# 7G_controller.net
KiCad netlist of a schematic drawn in EAGLE
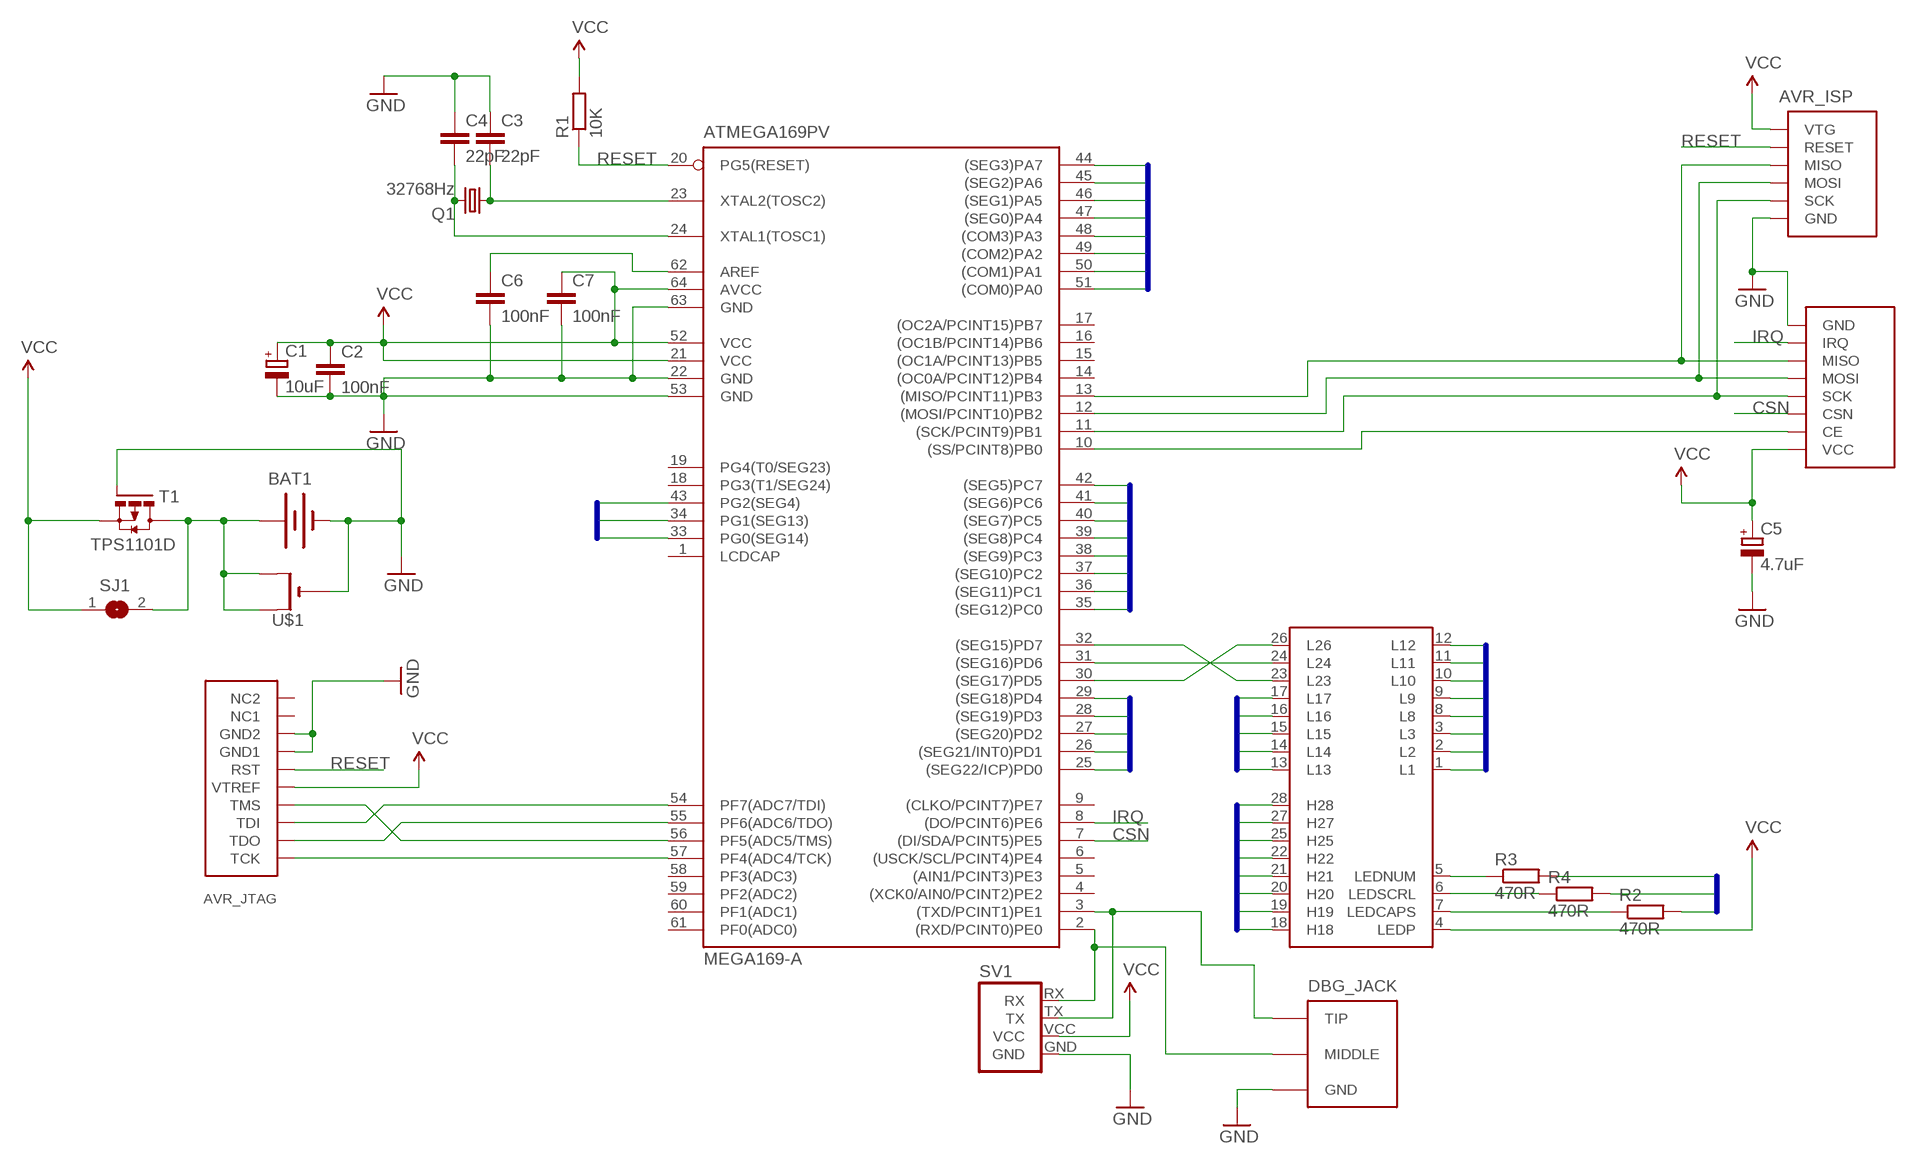
[diagram p0: schematic, sheet 1]

(export (version "E")
  (design (tool "Eeschema 10.0.6"))
  (components
    (comp (ref "ATMEGA169PV")
      (value "MEGA169-A")
      (footprint "eagle-import:TQFP64")
      (fields (field (name "MPN") "ATMEGA169PV-8AU"))
      (libsource (lib "eagle-import") (part "MEGA169-A"))
    )
    (comp (ref "AVR_ISP")
      (value "AVR-ISP-6SMALL_FP")
      (footprint "eagle-import:AVR-ISP-6-SMALL-FP")
      (libsource (lib "eagle-import") (part "AVR-ISP-6SMALL_FP"))
    )
    (comp (ref "AVR_JTAG")
      (value "AVR-JTAG")
      (footprint "eagle-import:AVR-JTAG")
      (libsource (lib "eagle-import") (part "AVR-JTAG"))
    )
    (comp (ref "BAT1")
      (value "BATTERYPLAIN")
      (footprint "eagle-import:BATTERY")
      (libsource (lib "eagle-import") (part "BATTERYPLAIN"))
    )
    (comp (ref "C1")
      (value "10uF")
      (footprint "eagle-import:SMC_B")
      (libsource (lib "eagle-import") (part "CPOL-EUSMCB"))
    )
    (comp (ref "C2")
      (value "100nF")
      (footprint "eagle-import:C0805")
      (libsource (lib "eagle-import") (part "C-EUC0805"))
    )
    (comp (ref "C3")
      (value "22pF")
      (footprint "eagle-import:C0805")
      (libsource (lib "eagle-import") (part "C-EUC0805"))
    )
    (comp (ref "C4")
      (value "22pF")
      (footprint "eagle-import:C0805")
      (libsource (lib "eagle-import") (part "C-EUC0805"))
    )
    (comp (ref "C5")
      (value "4.7uF")
      (footprint "eagle-import:SMC_B")
      (libsource (lib "eagle-import") (part "CPOL-EUSMCB"))
    )
    (comp (ref "C6")
      (value "100nF")
      (footprint "eagle-import:C0805")
      (libsource (lib "eagle-import") (part "C-EUC0805"))
    )
    (comp (ref "C7")
      (value "100nF")
      (footprint "eagle-import:C0805")
      (libsource (lib "eagle-import") (part "C-EUC0805"))
    )
    (comp (ref "DBG_JACK")
      (value "JACK_FEMALE_3.5MMCHEAP")
      (footprint "eagle-import:JACK_CHEAP")
      (libsource (lib "eagle-import") (part "JACK_FEMALE_3.5MMCHEAP"))
    )
    (comp (ref "MTRX_CONN")
      (value "SS7G_CONNSMD")
      (footprint "eagle-import:SS7G_CONN_SMD")
      (libsource (lib "eagle-import") (part "SS7G_CONNSMD"))
    )
    (comp (ref "NRF24L01")
      (value "NRF24L01_MOD_NINE_EAGLESGENERIC")
      (footprint "eagle-import:NRF24L01_MOD_GENERIC")
      (libsource (lib "eagle-import") (part "NRF24L01_MOD_NINE_EAGLESGENERIC"))
    )
    (comp (ref "Q1")
      (value "32768Hz")
      (footprint "eagle-import:NSK_QUARTZ_CLOCK")
      (libsource (lib "eagle-import") (part "CRYSTAL"))
    )
    (comp (ref "R1")
      (value "10K")
      (footprint "eagle-import:R0805")
      (libsource (lib "eagle-import") (part "R-EU_R0805"))
    )
    (comp (ref "R2")
      (value "470R")
      (footprint "eagle-import:R0805")
      (libsource (lib "eagle-import") (part "R-EU_R0805"))
    )
    (comp (ref "R3")
      (value "470R")
      (footprint "eagle-import:R0805")
      (libsource (lib "eagle-import") (part "R-EU_R0805"))
    )
    (comp (ref "R4")
      (value "470R")
      (footprint "eagle-import:R0805")
      (libsource (lib "eagle-import") (part "R-EU_R0805"))
    )
    (comp (ref "SJ1") (value "SJ") (footprint "eagle-import:SJ") (libsource (lib "eagle-import") (part "SJ")))
    (comp (ref "SV1")
      (value "UART_PORT")
      (footprint "eagle-import:UART_PORT")
      (libsource (lib "eagle-import") (part "UART_PORT"))
    )
    (comp (ref "T1")
      (value "TPS1101D")
      (footprint "eagle-import:SO8")
      (libsource (lib "eagle-import") (part "TPS1101D"))
    )
    (comp (ref "U$1")
      (value "CR2032SMT")
      (footprint "eagle-import:CR2032-SMD")
      (libsource (lib "eagle-import") (part "CR2032SMT"))
    )
  )
  (nets
    (net (code "1") (name "/CAPS") (class "Default")
      (node (ref "ATMEGA169PV") (pin "43") (pinfunction "PG2(SEG4)_43") (pintype "bidirectional"))
      (node (ref "R2") (pin "2") (pinfunction "2_2") (pintype "passive"))
    )
    (net (code "2") (name "/CSN") (class "Default")
      (node (ref "ATMEGA169PV") (pin "7") (pinfunction "(DI/SDA/PCINT5)PE5_7") (pintype "bidirectional"))
      (node (ref "NRF24L01") (pin "CSN") (pinfunction "CSN_CSN") (pintype "input"))
    )
    (net (code "3") (name "/H18") (class "Default")
      (node (ref "ATMEGA169PV") (pin "42") (pinfunction "(SEG5)PC7_42") (pintype "output"))
      (node (ref "MTRX_CONN") (pin "18") (pinfunction "H18_18") (pintype "bidirectional"))
    )
    (net (code "4") (name "/H19") (class "Default")
      (node (ref "ATMEGA169PV") (pin "41") (pinfunction "(SEG6)PC6_41") (pintype "output"))
      (node (ref "MTRX_CONN") (pin "19") (pinfunction "H19_19") (pintype "bidirectional"))
    )
    (net (code "5") (name "/H20") (class "Default")
      (node (ref "ATMEGA169PV") (pin "40") (pinfunction "(SEG7)PC5_40") (pintype "output"))
      (node (ref "MTRX_CONN") (pin "20") (pinfunction "H20_20") (pintype "bidirectional"))
    )
    (net (code "6") (name "/H21") (class "Default")
      (node (ref "ATMEGA169PV") (pin "38") (pinfunction "(SEG9)PC3_38") (pintype "output"))
      (node (ref "MTRX_CONN") (pin "21") (pinfunction "H21_21") (pintype "bidirectional"))
    )
    (net (code "7") (name "/H22") (class "Default")
      (node (ref "ATMEGA169PV") (pin "36") (pinfunction "(SEG11)PC1_36") (pintype "output"))
      (node (ref "MTRX_CONN") (pin "22") (pinfunction "H22_22") (pintype "bidirectional"))
    )
    (net (code "8") (name "/H25") (class "Default")
      (node (ref "ATMEGA169PV") (pin "35") (pinfunction "(SEG12)PC0_35") (pintype "output"))
      (node (ref "MTRX_CONN") (pin "25") (pinfunction "H25_25") (pintype "bidirectional"))
    )
    (net (code "9") (name "/H27") (class "Default")
      (node (ref "ATMEGA169PV") (pin "37") (pinfunction "(SEG10)PC2_37") (pintype "output"))
      (node (ref "MTRX_CONN") (pin "27") (pinfunction "H27_27") (pintype "bidirectional"))
    )
    (net (code "10") (name "/H28") (class "Default")
      (node (ref "ATMEGA169PV") (pin "39") (pinfunction "(SEG8)PC4_39") (pintype "output"))
      (node (ref "MTRX_CONN") (pin "28") (pinfunction "H28_28") (pintype "bidirectional"))
    )
    (net (code "11") (name "/IRQ") (class "Default")
      (node (ref "ATMEGA169PV") (pin "8") (pinfunction "(DO/PCINT6)PE6_8") (pintype "bidirectional"))
      (node (ref "NRF24L01") (pin "IRQ") (pinfunction "IRQ_IRQ") (pintype "output"))
    )
    (net (code "12") (name "/L1") (class "Default")
      (node (ref "ATMEGA169PV") (pin "50") (pinfunction "(COM1)PA1_50") (pintype "bidirectional"))
      (node (ref "MTRX_CONN") (pin "1") (pinfunction "L1_1") (pintype "bidirectional"))
    )
    (net (code "13") (name "/L2") (class "Default")
      (node (ref "ATMEGA169PV") (pin "48") (pinfunction "(COM3)PA3_48") (pintype "bidirectional"))
      (node (ref "MTRX_CONN") (pin "2") (pinfunction "L2_2") (pintype "bidirectional"))
    )
    (net (code "14") (name "/L3") (class "Default")
      (node (ref "ATMEGA169PV") (pin "46") (pinfunction "(SEG1)PA5_46") (pintype "bidirectional"))
      (node (ref "MTRX_CONN") (pin "3") (pinfunction "L3_3") (pintype "bidirectional"))
    )
    (net (code "15") (name "/L8") (class "Default")
      (node (ref "ATMEGA169PV") (pin "45") (pinfunction "(SEG2)PA6_45") (pintype "bidirectional"))
      (node (ref "MTRX_CONN") (pin "8") (pinfunction "L8_8") (pintype "bidirectional"))
    )
    (net (code "16") (name "/L9") (class "Default")
      (node (ref "ATMEGA169PV") (pin "44") (pinfunction "(SEG3)PA7_44") (pintype "bidirectional"))
      (node (ref "MTRX_CONN") (pin "9") (pinfunction "L9_9") (pintype "bidirectional"))
    )
    (net (code "17") (name "/L10") (class "Default")
      (node (ref "ATMEGA169PV") (pin "25") (pinfunction "(SEG22/ICP)PD0_25") (pintype "bidirectional"))
      (node (ref "MTRX_CONN") (pin "10") (pinfunction "L10_10") (pintype "bidirectional"))
    )
    (net (code "18") (name "/L11") (class "Default")
      (node (ref "ATMEGA169PV") (pin "26") (pinfunction "(SEG21/INT0)PD1_26") (pintype "bidirectional"))
      (node (ref "MTRX_CONN") (pin "11") (pinfunction "L11_11") (pintype "bidirectional"))
    )
    (net (code "19") (name "/L12") (class "Default")
      (node (ref "ATMEGA169PV") (pin "27") (pinfunction "(SEG20)PD2_27") (pintype "bidirectional"))
      (node (ref "MTRX_CONN") (pin "12") (pinfunction "L12_12") (pintype "bidirectional"))
    )
    (net (code "20") (name "/L13") (class "Default")
      (node (ref "ATMEGA169PV") (pin "28") (pinfunction "(SEG19)PD3_28") (pintype "bidirectional"))
      (node (ref "MTRX_CONN") (pin "13") (pinfunction "L13_13") (pintype "bidirectional"))
    )
    (net (code "21") (name "/L14") (class "Default")
      (node (ref "ATMEGA169PV") (pin "29") (pinfunction "(SEG18)PD4_29") (pintype "bidirectional"))
      (node (ref "MTRX_CONN") (pin "14") (pinfunction "L14_14") (pintype "bidirectional"))
    )
    (net (code "22") (name "/L15") (class "Default")
      (node (ref "ATMEGA169PV") (pin "51") (pinfunction "(COM0)PA0_51") (pintype "bidirectional"))
      (node (ref "MTRX_CONN") (pin "15") (pinfunction "L15_15") (pintype "bidirectional"))
    )
    (net (code "23") (name "/L16") (class "Default")
      (node (ref "ATMEGA169PV") (pin "49") (pinfunction "(COM2)PA2_49") (pintype "bidirectional"))
      (node (ref "MTRX_CONN") (pin "16") (pinfunction "L16_16") (pintype "bidirectional"))
    )
    (net (code "24") (name "/L17") (class "Default")
      (node (ref "ATMEGA169PV") (pin "47") (pinfunction "(SEG0)PA4_47") (pintype "bidirectional"))
      (node (ref "MTRX_CONN") (pin "17") (pinfunction "L17_17") (pintype "bidirectional"))
    )
    (net (code "25") (name "/NUML") (class "Default")
      (node (ref "ATMEGA169PV") (pin "33") (pinfunction "PG0(SEG14)_33") (pintype "bidirectional"))
      (node (ref "R3") (pin "2") (pinfunction "2_2") (pintype "passive"))
    )
    (net (code "26") (name "/RESET") (class "Default")
      (node (ref "ATMEGA169PV") (pin "20") (pinfunction "PG5(RESET)_20") (pintype "input"))
      (node (ref "AVR_ISP") (pin "RESET") (pinfunction "RESET_RESET") (pintype "passive"))
      (node (ref "AVR_JTAG") (pin "P$6") (pinfunction "RST_P$6") (pintype "bidirectional"))
      (node (ref "R1") (pin "1") (pinfunction "1_1") (pintype "passive"))
    )
    (net (code "27") (name "/SCRL") (class "Default")
      (node (ref "ATMEGA169PV") (pin "34") (pinfunction "PG1(SEG13)_34") (pintype "bidirectional"))
      (node (ref "R4") (pin "2") (pinfunction "2_2") (pintype "passive"))
    )
    (net (code "28") (name "GND") (class "Default")
      (node (ref "ATMEGA169PV") (pin "22") (pinfunction "GND_22") (pintype "power_in"))
      (node (ref "ATMEGA169PV") (pin "53") (pinfunction "GND_53") (pintype "power_in"))
      (node (ref "ATMEGA169PV") (pin "63") (pinfunction "GND_63") (pintype "power_in"))
      (node (ref "AVR_ISP") (pin "GND") (pinfunction "GND_GND") (pintype "passive"))
      (node (ref "AVR_JTAG") (pin "P$10") (pinfunction "GND2_P$10") (pintype "power_in"))
      (node (ref "AVR_JTAG") (pin "P$2") (pinfunction "GND1_P$2") (pintype "power_in"))
      (node (ref "BAT1") (pin "-") (pinfunction "-_-") (pintype "power_in"))
      (node (ref "C1") (pin "-") (pinfunction "-_-") (pintype "passive"))
      (node (ref "C2") (pin "2") (pinfunction "2_2") (pintype "passive"))
      (node (ref "C3") (pin "1") (pinfunction "1_1") (pintype "passive"))
      (node (ref "C4") (pin "1") (pinfunction "1_1") (pintype "passive"))
      (node (ref "C5") (pin "-") (pinfunction "-_-") (pintype "passive"))
      (node (ref "C6") (pin "2") (pinfunction "2_2") (pintype "passive"))
      (node (ref "C7") (pin "2") (pinfunction "2_2") (pintype "passive"))
      (node (ref "DBG_JACK") (pin "1") (pinfunction "GND_1") (pintype "bidirectional"))
      (node (ref "NRF24L01") (pin "GND") (pinfunction "GND_GND") (pintype "power_in"))
      (node (ref "SV1") (pin "GND") (pinfunction "GND_GND") (pintype "passive"))
      (node (ref "T1") (pin "4") (pinfunction "G_4") (pintype "passive"))
      (node (ref "U$1") (pin "-") (pinfunction "-_-") (pintype "passive"))
    )
    (net (code "29") (name "Net-(ATMEGA169PV-(MISO{slash}PCINT11)PB3)") (class "Default")
      (node (ref "ATMEGA169PV") (pin "13") (pinfunction "(MISO/PCINT11)PB3_13") (pintype "bidirectional"))
      (node (ref "AVR_ISP") (pin "MISO") (pinfunction "MISO_MISO") (pintype "passive"))
      (node (ref "NRF24L01") (pin "MISO") (pinfunction "MISO_MISO") (pintype "output"))
    )
    (net (code "30") (name "Net-(ATMEGA169PV-(MOSI{slash}PCINT10)PB2)") (class "Default")
      (node (ref "ATMEGA169PV") (pin "12") (pinfunction "(MOSI/PCINT10)PB2_12") (pintype "bidirectional"))
      (node (ref "AVR_ISP") (pin "MOSI") (pinfunction "MOSI_MOSI") (pintype "passive"))
      (node (ref "NRF24L01") (pin "MOSI") (pinfunction "MOSI_MOSI") (pintype "input"))
    )
    (net (code "31") (name "Net-(ATMEGA169PV-(RXD{slash}PCINT0)PE0)") (class "Default")
      (node (ref "ATMEGA169PV") (pin "2") (pinfunction "(RXD/PCINT0)PE0_2") (pintype "bidirectional"))
      (node (ref "DBG_JACK") (pin "4") (pinfunction "MIDDLE_4") (pintype "bidirectional"))
      (node (ref "SV1") (pin "RX") (pinfunction "RX_RX") (pintype "passive"))
    )
    (net (code "32") (name "Net-(ATMEGA169PV-(SCK{slash}PCINT9)PB1)") (class "Default")
      (node (ref "ATMEGA169PV") (pin "11") (pinfunction "(SCK/PCINT9)PB1_11") (pintype "bidirectional"))
      (node (ref "AVR_ISP") (pin "SCK") (pinfunction "SCK_SCK") (pintype "passive"))
      (node (ref "NRF24L01") (pin "SCK") (pinfunction "SCK_SCK") (pintype "input"))
    )
    (net (code "33") (name "Net-(ATMEGA169PV-(SEG15)PD7)") (class "Default")
      (node (ref "ATMEGA169PV") (pin "32") (pinfunction "(SEG15)PD7_32") (pintype "bidirectional"))
      (node (ref "MTRX_CONN") (pin "23") (pinfunction "L23_23") (pintype "bidirectional"))
    )
    (net (code "34") (name "Net-(ATMEGA169PV-(SEG16)PD6)") (class "Default")
      (node (ref "ATMEGA169PV") (pin "31") (pinfunction "(SEG16)PD6_31") (pintype "bidirectional"))
      (node (ref "MTRX_CONN") (pin "24") (pinfunction "L24_24") (pintype "bidirectional"))
    )
    (net (code "35") (name "Net-(ATMEGA169PV-(SEG17)PD5)") (class "Default")
      (node (ref "ATMEGA169PV") (pin "30") (pinfunction "(SEG17)PD5_30") (pintype "bidirectional"))
      (node (ref "MTRX_CONN") (pin "26") (pinfunction "L26_26") (pintype "bidirectional"))
    )
    (net (code "36") (name "Net-(ATMEGA169PV-(SS{slash}PCINT8)PB0)") (class "Default")
      (node (ref "ATMEGA169PV") (pin "10") (pinfunction "(SS/PCINT8)PB0_10") (pintype "bidirectional"))
      (node (ref "NRF24L01") (pin "CE") (pinfunction "CE_CE") (pintype "input"))
    )
    (net (code "37") (name "Net-(ATMEGA169PV-(TXD{slash}PCINT1)PE1)") (class "Default")
      (node (ref "ATMEGA169PV") (pin "3") (pinfunction "(TXD/PCINT1)PE1_3") (pintype "bidirectional"))
      (node (ref "DBG_JACK") (pin "2") (pinfunction "TIP_2") (pintype "bidirectional"))
      (node (ref "DBG_JACK") (pin "3") (pinfunction "TIP_3") (pintype "bidirectional"))
      (node (ref "SV1") (pin "TX") (pinfunction "TX_TX") (pintype "passive"))
    )
    (net (code "38") (name "Net-(ATMEGA169PV-AREF)") (class "Default")
      (node (ref "ATMEGA169PV") (pin "62") (pinfunction "AREF_62") (pintype "passive"))
      (node (ref "C6") (pin "1") (pinfunction "1_1") (pintype "passive"))
    )
    (net (code "39") (name "Net-(ATMEGA169PV-PF4(ADC4{slash}TCK))") (class "Default")
      (node (ref "ATMEGA169PV") (pin "57") (pinfunction "PF4(ADC4/TCK)_57") (pintype "input"))
      (node (ref "AVR_JTAG") (pin "P$1") (pinfunction "TCK_P$1") (pintype "bidirectional"))
    )
    (net (code "40") (name "Net-(ATMEGA169PV-PF5(ADC5{slash}TMS))") (class "Default")
      (node (ref "ATMEGA169PV") (pin "56") (pinfunction "PF5(ADC5/TMS)_56") (pintype "input"))
      (node (ref "AVR_JTAG") (pin "P$5") (pinfunction "TMS_P$5") (pintype "bidirectional"))
    )
    (net (code "41") (name "Net-(ATMEGA169PV-PF6(ADC6{slash}TDO))") (class "Default")
      (node (ref "ATMEGA169PV") (pin "55") (pinfunction "PF6(ADC6/TDO)_55") (pintype "input"))
      (node (ref "AVR_JTAG") (pin "P$3") (pinfunction "TDO_P$3") (pintype "bidirectional"))
    )
    (net (code "42") (name "Net-(ATMEGA169PV-PF7(ADC7{slash}TDI))") (class "Default")
      (node (ref "ATMEGA169PV") (pin "54") (pinfunction "PF7(ADC7/TDI)_54") (pintype "input"))
      (node (ref "AVR_JTAG") (pin "P$9") (pinfunction "TDI_P$9") (pintype "bidirectional"))
    )
    (net (code "43") (name "Net-(ATMEGA169PV-XTAL1(TOSC1))") (class "Default")
      (node (ref "ATMEGA169PV") (pin "24") (pinfunction "XTAL1(TOSC1)_24") (pintype "bidirectional"))
      (node (ref "C4") (pin "2") (pinfunction "2_2") (pintype "passive"))
      (node (ref "Q1") (pin "4") (pinfunction "2_4") (pintype "passive"))
    )
    (net (code "44") (name "Net-(ATMEGA169PV-XTAL2(TOSC2))") (class "Default")
      (node (ref "ATMEGA169PV") (pin "23") (pinfunction "XTAL2(TOSC2)_23") (pintype "bidirectional"))
      (node (ref "C3") (pin "2") (pinfunction "2_2") (pintype "passive"))
      (node (ref "Q1") (pin "1") (pinfunction "1_1") (pintype "passive"))
    )
    (net (code "45") (name "Net-(MTRX_CONN-LEDCAPS)") (class "Default")
      (node (ref "MTRX_CONN") (pin "7") (pinfunction "LEDCAPS_7") (pintype "bidirectional"))
      (node (ref "R2") (pin "1") (pinfunction "1_1") (pintype "passive"))
    )
    (net (code "46") (name "Net-(MTRX_CONN-LEDNUM)") (class "Default")
      (node (ref "MTRX_CONN") (pin "5") (pinfunction "LEDNUM_5") (pintype "bidirectional"))
      (node (ref "R3") (pin "1") (pinfunction "1_1") (pintype "passive"))
    )
    (net (code "47") (name "Net-(MTRX_CONN-LEDSCRL)") (class "Default")
      (node (ref "MTRX_CONN") (pin "6") (pinfunction "LEDSCRL_6") (pintype "bidirectional"))
      (node (ref "R4") (pin "1") (pinfunction "1_1") (pintype "passive"))
    )
    (net (code "48") (name "Net-(U$1-+)") (class "Default")
      (node (ref "BAT1") (pin "+") (pinfunction "+_+") (pintype "power_in"))
      (node (ref "SJ1") (pin "2") (pinfunction "2_2") (pintype "passive"))
      (node (ref "T1") (pin "5") (pinfunction "D_5") (pintype "passive"))
      (node (ref "T1") (pin "6") (pinfunction "D_6") (pintype "passive"))
      (node (ref "T1") (pin "7") (pinfunction "D_7") (pintype "passive"))
      (node (ref "T1") (pin "8") (pinfunction "D_8") (pintype "passive"))
      (node (ref "U$1") (pin "+$1") (pinfunction "+_+$1") (pintype "passive"))
      (node (ref "U$1") (pin "+$2") (pinfunction "+1_+$2") (pintype "passive"))
    )
    (net (code "49") (name "VCC") (class "Default")
      (node (ref "ATMEGA169PV") (pin "21") (pinfunction "VCC_21") (pintype "power_in"))
      (node (ref "ATMEGA169PV") (pin "52") (pinfunction "VCC_52") (pintype "power_in"))
      (node (ref "ATMEGA169PV") (pin "64") (pinfunction "AVCC_64") (pintype "power_in"))
      (node (ref "AVR_ISP") (pin "VCC") (pinfunction "VTG_VCC") (pintype "passive"))
      (node (ref "AVR_JTAG") (pin "P$4") (pinfunction "VTREF_P$4") (pintype "bidirectional"))
      (node (ref "C1") (pin "+") (pinfunction "+_+") (pintype "passive"))
      (node (ref "C2") (pin "1") (pinfunction "1_1") (pintype "passive"))
      (node (ref "C5") (pin "+") (pinfunction "+_+") (pintype "passive"))
      (node (ref "C7") (pin "1") (pinfunction "1_1") (pintype "passive"))
      (node (ref "MTRX_CONN") (pin "4") (pinfunction "LEDP_4") (pintype "bidirectional"))
      (node (ref "NRF24L01") (pin "+3.3V") (pinfunction "VCC_+3.3V") (pintype "power_in"))
      (node (ref "R1") (pin "2") (pinfunction "2_2") (pintype "passive"))
      (node (ref "SJ1") (pin "1") (pinfunction "1_1") (pintype "passive"))
      (node (ref "SV1") (pin "VCC") (pinfunction "VCC_VCC") (pintype "passive"))
      (node (ref "T1") (pin "1") (pinfunction "S_1") (pintype "passive"))
      (node (ref "T1") (pin "2") (pinfunction "S_2") (pintype "passive"))
      (node (ref "T1") (pin "3") (pinfunction "S_3") (pintype "passive"))
    )
    (net (code "50") (name "unconnected-(ATMEGA169PV-(AIN1{slash}PCINT3)PE3-Pad5)") (class "Default")
      (node (ref "ATMEGA169PV") (pin "5") (pinfunction "(AIN1/PCINT3)PE3_5") (pintype "bidirectional"))
    )
    (net (code "51") (name "unconnected-(ATMEGA169PV-(CLKO{slash}PCINT7)PE7-Pad9)") (class "Default")
      (node (ref "ATMEGA169PV") (pin "9") (pinfunction "(CLKO/PCINT7)PE7_9") (pintype "bidirectional"))
    )
    (net (code "52") (name "unconnected-(ATMEGA169PV-(OC0A{slash}PCINT12)PB4-Pad14)") (class "Default")
      (node (ref "ATMEGA169PV") (pin "14") (pinfunction "(OC0A/PCINT12)PB4_14") (pintype "bidirectional"))
    )
    (net (code "53") (name "unconnected-(ATMEGA169PV-(OC1A{slash}PCINT13)PB5-Pad15)") (class "Default")
      (node (ref "ATMEGA169PV") (pin "15") (pinfunction "(OC1A/PCINT13)PB5_15") (pintype "bidirectional"))
    )
    (net (code "54") (name "unconnected-(ATMEGA169PV-(OC1B{slash}PCINT14)PB6-Pad16)") (class "Default")
      (node (ref "ATMEGA169PV") (pin "16") (pinfunction "(OC1B/PCINT14)PB6_16") (pintype "bidirectional"))
    )
    (net (code "55") (name "unconnected-(ATMEGA169PV-(OC2A{slash}PCINT15)PB7-Pad17)") (class "Default")
      (node (ref "ATMEGA169PV") (pin "17") (pinfunction "(OC2A/PCINT15)PB7_17") (pintype "bidirectional"))
    )
    (net (code "56") (name "unconnected-(ATMEGA169PV-(USCK{slash}SCL{slash}PCINT4)PE4-Pad6)") (class "Default")
      (node (ref "ATMEGA169PV") (pin "6") (pinfunction "(USCK/SCL/PCINT4)PE4_6") (pintype "bidirectional"))
    )
    (net (code "57") (name "unconnected-(ATMEGA169PV-(XCK0{slash}AIN0{slash}PCINT2)PE2-Pad4)") (class "Default")
      (node (ref "ATMEGA169PV") (pin "4") (pinfunction "(XCK0/AIN0/PCINT2)PE2_4") (pintype "bidirectional"))
    )
    (net (code "58") (name "unconnected-(ATMEGA169PV-LCDCAP-Pad1)") (class "Default")
      (node (ref "ATMEGA169PV") (pin "1") (pinfunction "LCDCAP_1") (pintype "input"))
    )
    (net (code "59") (name "unconnected-(ATMEGA169PV-PF0(ADC0)-Pad61)") (class "Default")
      (node (ref "ATMEGA169PV") (pin "61") (pinfunction "PF0(ADC0)_61") (pintype "input"))
    )
    (net (code "60") (name "unconnected-(ATMEGA169PV-PF1(ADC1)-Pad60)") (class "Default")
      (node (ref "ATMEGA169PV") (pin "60") (pinfunction "PF1(ADC1)_60") (pintype "input"))
    )
    (net (code "61") (name "unconnected-(ATMEGA169PV-PF2(ADC2)-Pad59)") (class "Default")
      (node (ref "ATMEGA169PV") (pin "59") (pinfunction "PF2(ADC2)_59") (pintype "input"))
    )
    (net (code "62") (name "unconnected-(ATMEGA169PV-PF3(ADC3)-Pad58)") (class "Default")
      (node (ref "ATMEGA169PV") (pin "58") (pinfunction "PF3(ADC3)_58") (pintype "input"))
    )
    (net (code "63") (name "unconnected-(ATMEGA169PV-PG3(T1{slash}SEG24)-Pad18)") (class "Default")
      (node (ref "ATMEGA169PV") (pin "18") (pinfunction "PG3(T1/SEG24)_18") (pintype "bidirectional"))
    )
    (net (code "64") (name "unconnected-(ATMEGA169PV-PG4(T0{slash}SEG23)-Pad19)") (class "Default")
      (node (ref "ATMEGA169PV") (pin "19") (pinfunction "PG4(T0/SEG23)_19") (pintype "bidirectional"))
    )
    (net (code "65") (name "unconnected-(AVR_JTAG-NC1-PadP$7)") (class "Default")
      (node (ref "AVR_JTAG") (pin "P$7") (pinfunction "NC1_P$7") (pintype "no_connect"))
    )
    (net (code "66") (name "unconnected-(AVR_JTAG-NC2-PadP$8)") (class "Default")
      (node (ref "AVR_JTAG") (pin "P$8") (pinfunction "NC2_P$8") (pintype "no_connect"))
    )
  )
)
